# blackfin_b_flash_jtag_serial.net
KiCad netlist of a schematic drawn in Altium Designer
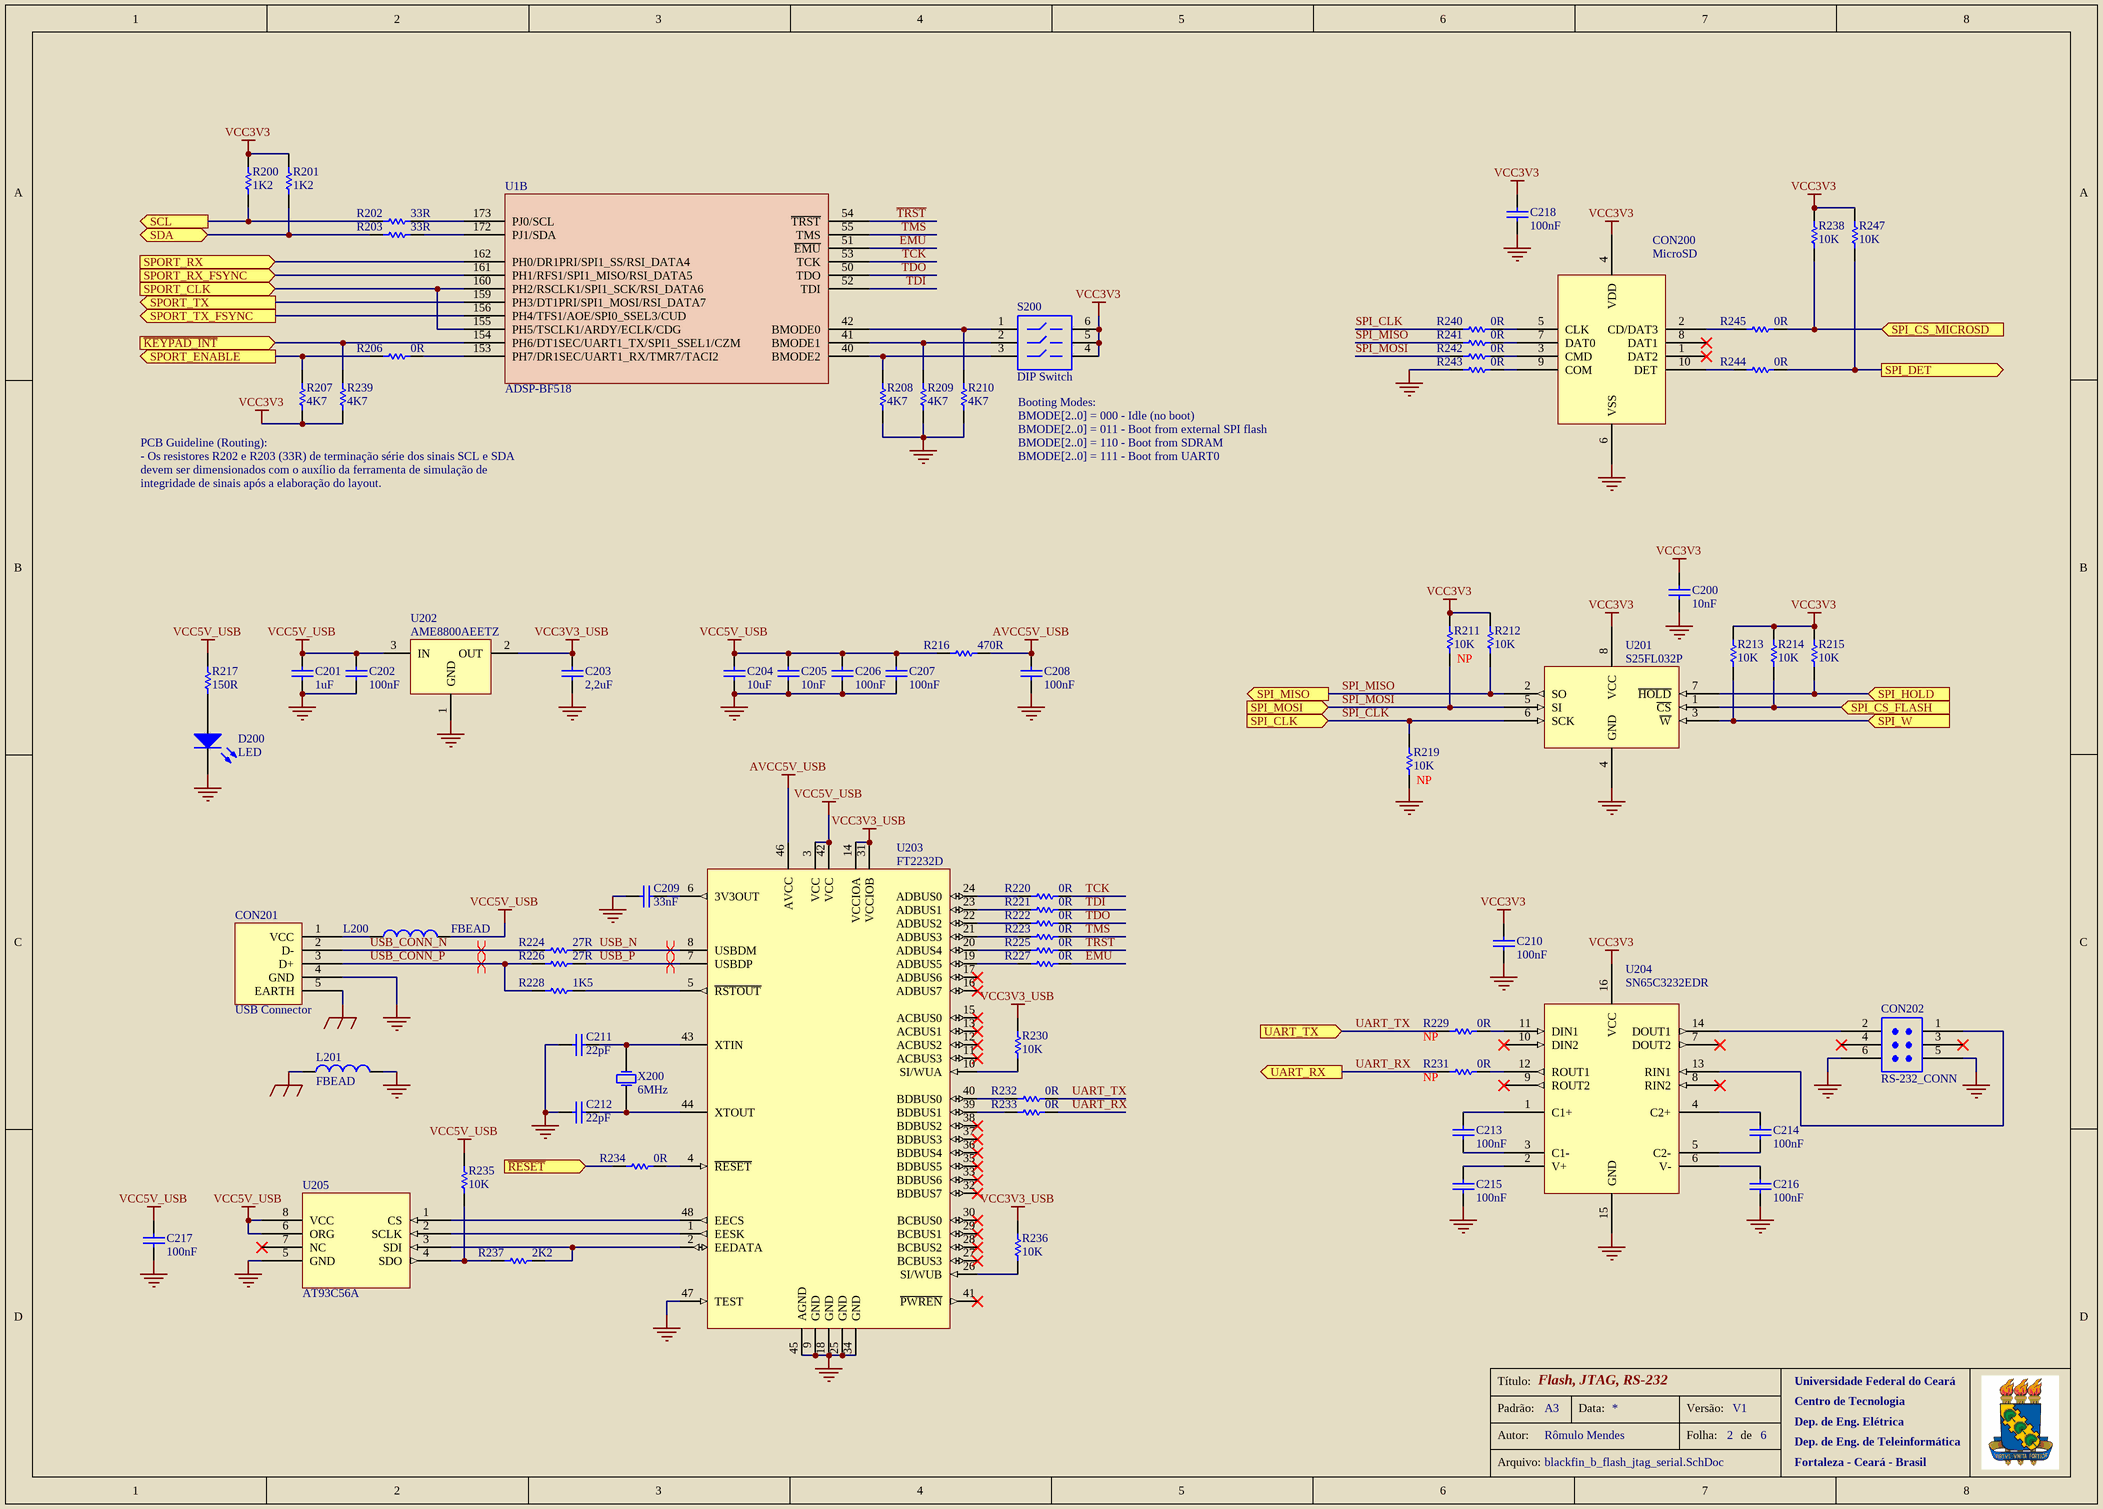
[diagram p0: blackfin_b_flash_jtag_serial.SchDoc]

(export (version "E")
  (design (tool "Eeschema 10.0.6"))
  (components
    (comp (ref "C200")
      (value "10nF")
      (footprint "blackfin_pcblib:C_0603")
      (fields
        (field (name "EVENDORPART#") "77-VJ0603Y103KXAPBC")
        (field (name "MANUFACTURER") "Vishay/Vitramon")
        (field (name "PART#") "VJ0603Y103KXAPW1BC")
      )
      (libsource (lib "blackfin_schlib") (part "Capacitor"))
    )
    (comp (ref "C201")
      (value "1uF")
      (footprint "blackfin_pcblib:C_0603")
      (fields
        (field (name "EVENDORPART#") "81-GRM188F51E105ZA12")
        (field (name "MANUFACTURER") "Murata")
        (field (name "PART#") "GRM188F51E105ZA12D")
      )
      (libsource (lib "blackfin_schlib") (part "Capacitor"))
    )
    (comp (ref "C202")
      (value "100nF")
      (footprint "blackfin_pcblib:C_0603")
      (fields
        (field (name "EVENDORPART#") "81-GRM188R71E104KA01")
        (field (name "MANUFACTURER") "Murata")
        (field (name "PART#") "GRM188R71E104KA01J")
      )
      (libsource (lib "blackfin_schlib") (part "Capacitor"))
    )
    (comp (ref "C203")
      (value "2,2uF")
      (footprint "blackfin_pcblib:C_0603")
      (fields
        (field (name "EVENDORPART#") "81-GRM188F51A225ZE01")
        (field (name "MANUFACTURER") "Murata")
        (field (name "PART#") "GRM188F51A225ZE01D")
      )
      (libsource (lib "blackfin_schlib") (part "Capacitor"))
    )
    (comp (ref "C204")
      (value "10uF")
      (footprint "blackfin_pcblib:C_0805")
      (fields
        (field (name "EVENDORPART#") "810-C2012Y5V1C106Z")
        (field (name "MANUFACTURER") "TDK")
        (field (name "PART#") "C2012Y5V1C106Z")
      )
      (libsource (lib "blackfin_schlib") (part "Capacitor"))
    )
    (comp (ref "C205")
      (value "10nF")
      (footprint "blackfin_pcblib:C_0603")
      (fields
        (field (name "EVENDORPART#") "77-VJ0603Y103KXAPBC")
        (field (name "MANUFACTURER") "Vishay/Vitramon")
        (field (name "PART#") "VJ0603Y103KXAPW1BC")
      )
      (libsource (lib "blackfin_schlib") (part "Capacitor"))
    )
    (comp (ref "C206")
      (value "100nF")
      (footprint "blackfin_pcblib:C_0603")
      (fields
        (field (name "EVENDORPART#") "81-GRM188R71E104KA01")
        (field (name "MANUFACTURER") "Murata")
        (field (name "PART#") "GRM188R71E104KA01J")
      )
      (libsource (lib "blackfin_schlib") (part "Capacitor"))
    )
    (comp (ref "C207")
      (value "100nF")
      (footprint "blackfin_pcblib:C_0603")
      (fields
        (field (name "EVENDORPART#") "81-GRM188R71E104KA01")
        (field (name "MANUFACTURER") "Murata")
        (field (name "PART#") "GRM188R71E104KA01J")
      )
      (libsource (lib "blackfin_schlib") (part "Capacitor"))
    )
    (comp (ref "C208")
      (value "100nF")
      (footprint "blackfin_pcblib:C_0603")
      (fields
        (field (name "EVENDORPART#") "81-GRM188R71E104KA01")
        (field (name "MANUFACTURER") "Murata")
        (field (name "PART#") "GRM188R71E104KA01J")
      )
      (libsource (lib "blackfin_schlib") (part "Capacitor"))
    )
    (comp (ref "C209")
      (value "33nF")
      (footprint "blackfin_pcblib:C_0603")
      (fields
        (field (name "EVENDORPART#") "81-GRM18B11E333KA01D")
        (field (name "MANUFACTURER") "Murata")
        (field (name "PART#") "GRM188B11E333KA01D")
      )
      (libsource (lib "blackfin_schlib") (part "Capacitor"))
    )
    (comp (ref "C210")
      (value "100nF")
      (footprint "blackfin_pcblib:C_0603")
      (fields
        (field (name "EVENDORPART#") "81-GRM188R71E104KA01")
        (field (name "MANUFACTURER") "Murata")
        (field (name "PART#") "GRM188R71E104KA01J")
      )
      (libsource (lib "blackfin_schlib") (part "Capacitor"))
    )
    (comp (ref "C211")
      (value "22pF")
      (footprint "blackfin_pcblib:C_0603")
      (fields
        (field (name "EVENDORPART#") "581-06035A220J")
        (field (name "MANUFACTURER") "AVX")
        (field (name "PART#") "06035A220JAT2A")
      )
      (libsource (lib "blackfin_schlib") (part "Capacitor"))
    )
    (comp (ref "C212")
      (value "22pF")
      (footprint "blackfin_pcblib:C_0603")
      (fields
        (field (name "EVENDORPART#") "581-06035A220J")
        (field (name "MANUFACTURER") "AVX")
        (field (name "PART#") "06035A220JAT2A")
      )
      (libsource (lib "blackfin_schlib") (part "Capacitor"))
    )
    (comp (ref "C213")
      (value "100nF")
      (footprint "blackfin_pcblib:C_0603")
      (fields
        (field (name "EVENDORPART#") "81-GRM188R71E104KA01")
        (field (name "MANUFACTURER") "Murata")
        (field (name "PART#") "GRM188R71E104KA01J")
      )
      (libsource (lib "blackfin_schlib") (part "Capacitor"))
    )
    (comp (ref "C214")
      (value "100nF")
      (footprint "blackfin_pcblib:C_0603")
      (fields
        (field (name "EVENDORPART#") "81-GRM188R71E104KA01")
        (field (name "MANUFACTURER") "Murata")
        (field (name "PART#") "GRM188R71E104KA01J")
      )
      (libsource (lib "blackfin_schlib") (part "Capacitor"))
    )
    (comp (ref "C215")
      (value "100nF")
      (footprint "blackfin_pcblib:C_0603")
      (fields
        (field (name "EVENDORPART#") "81-GRM188R71E104KA01")
        (field (name "MANUFACTURER") "Murata")
        (field (name "PART#") "GRM188R71E104KA01J")
      )
      (libsource (lib "blackfin_schlib") (part "Capacitor"))
    )
    (comp (ref "C216")
      (value "100nF")
      (footprint "blackfin_pcblib:C_0603")
      (fields
        (field (name "EVENDORPART#") "81-GRM188R71E104KA01")
        (field (name "MANUFACTURER") "Murata")
        (field (name "PART#") "GRM188R71E104KA01J")
      )
      (libsource (lib "blackfin_schlib") (part "Capacitor"))
    )
    (comp (ref "C217")
      (value "100nF")
      (footprint "blackfin_pcblib:C_0603")
      (fields
        (field (name "EVENDORPART#") "81-GRM188R71E104KA01")
        (field (name "MANUFACTURER") "Murata")
        (field (name "PART#") "GRM188R71E104KA01J")
      )
      (libsource (lib "blackfin_schlib") (part "Capacitor"))
    )
    (comp (ref "C218")
      (value "100nF")
      (footprint "blackfin_pcblib:C_0603")
      (fields
        (field (name "EVENDORPART#") "81-GRM188R71E104KA01")
        (field (name "MANUFACTURER") "Murata")
        (field (name "PART#") "GRM188R71E104KA01J")
      )
      (libsource (lib "blackfin_schlib") (part "Capacitor"))
    )
    (comp (ref "CON200")
      (value "MicroSD")
      (footprint "blackfin_pcblib:MICRO_SD")
      (fields
        (field (name "MANUFACTURER") "AVX Corporation")
        (field (name "PART#") "045138008010890+")
        (field (name "EVENDORPART#") "478-4965-1-ND")
      )
      (libsource (lib "blackfin_schlib") (part "MicroSD"))
    )
    (comp (ref "CON201")
      (value "USB Connector")
      (footprint "blackfin_pcblib:USB Connector")
      (fields
        (field (name "EVENDORPART#") "649-61729-0010BLF")
        (field (name "MANUFACTURER") "FCI")
        (field (name "PART#") "61729-0010BLF")
      )
      (libsource (lib "blackfin_schlib") (part "USB Connector"))
    )
    (comp (ref "CON202")
      (value "RS-232_CONN")
      (footprint "blackfin_pcblib:Header_2x3")
      (fields
        (field (name "PART#") "87759-0614")
        (field (name "EVENDORPART#") "538-87759-0614")
        (field (name "MANUFACTURER") "Molex")
      )
      (libsource (lib "blackfin_schlib") (part "RS-232 Connector"))
    )
    (comp (ref "D200")
      (value "LED")
      (footprint "blackfin_pcblib:LED_0603")
      (description "Red LED")
      (fields (field (name "EVENDORPART#") "638-QTLP600C2TR") (field (name "MANUFACTURER") "Everlight"))
      (libsource (lib "blackfin_schlib") (part "LED"))
    )
    (comp (ref "L200")
      (value "FBEAD")
      (footprint "blackfin_pcblib:L_0603")
      (fields
        (field (name "EVENDORPART#") "875-MI0603L301R-10")
        (field (name "MANUFACTURER") "Laird Technologies")
        (field (name "PART#") "MI0603L301R-10")
      )
      (libsource (lib "blackfin_schlib") (part "Inductor"))
    )
    (comp (ref "L201")
      (value "FBEAD")
      (footprint "blackfin_pcblib:L_0603")
      (fields
        (field (name "EVENDORPART#") "875-MI0603L301R-10")
        (field (name "MANUFACTURER") "Laird Technologies")
        (field (name "PART#") "MI0603L301R-10")
      )
      (libsource (lib "blackfin_schlib") (part "Inductor"))
    )
    (comp (ref "R200")
      (value "1K2")
      (footprint "blackfin_pcblib:R_0603")
      (fields
        (field (name "EVENDORPART#") "71-CRCW0603-1.2K-E3")
        (field (name "PART#") "CRCW06031K20FKEA")
        (field (name "MANUFACTURER") "Vishay/Dale")
      )
      (libsource (lib "blackfin_schlib") (part "Resistor"))
    )
    (comp (ref "R201")
      (value "1K2")
      (footprint "blackfin_pcblib:R_0603")
      (fields
        (field (name "EVENDORPART#") "71-CRCW0603-1.2K-E3")
        (field (name "PART#") "CRCW06031K20FKEA")
        (field (name "MANUFACTURER") "Vishay/Dale")
      )
      (libsource (lib "blackfin_schlib") (part "Resistor"))
    )
    (comp (ref "R202")
      (value "33R")
      (footprint "blackfin_pcblib:R_0402")
      (fields
        (field (name "EVENDORPART#") "71-CRCW0402J-33-E3")
        (field (name "PART#") "CRCW040233R0JNED")
        (field (name "MANUFACTURER") "Vishay/Dale")
      )
      (libsource (lib "blackfin_schlib") (part "Resistor"))
    )
    (comp (ref "R203")
      (value "33R")
      (footprint "blackfin_pcblib:R_0402")
      (fields
        (field (name "EVENDORPART#") "71-CRCW0402J-33-E3")
        (field (name "PART#") "CRCW040233R0JNED")
        (field (name "MANUFACTURER") "Vishay/Dale")
      )
      (libsource (lib "blackfin_schlib") (part "Resistor"))
    )
    (comp (ref "R206")
      (value "0R")
      (footprint "blackfin_pcblib:R_0603")
      (fields
        (field (name "EVENDORPART#") "71-CRCW06030000Z0EB")
        (field (name "PART#") "CRCW06030000Z0EB")
        (field (name "MANUFACTURER") "Vishay/Dale")
      )
      (libsource (lib "blackfin_schlib") (part "Resistor"))
    )
    (comp (ref "R207")
      (value "4K7")
      (footprint "blackfin_pcblib:R_0603")
      (fields
        (field (name "EVENDORPART#") "71-CRCW0603J-4.7K-E3")
        (field (name "PART#") "CRCW06034K70JNEA")
        (field (name "MANUFACTURER") "Vishay/Dale")
      )
      (libsource (lib "blackfin_schlib") (part "Resistor"))
    )
    (comp (ref "R208")
      (value "4K7")
      (footprint "blackfin_pcblib:R_0603")
      (fields
        (field (name "EVENDORPART#") "71-CRCW0603J-4.7K-E3")
        (field (name "PART#") "CRCW06034K70JNEA")
        (field (name "MANUFACTURER") "Vishay/Dale")
      )
      (libsource (lib "blackfin_schlib") (part "Resistor"))
    )
    (comp (ref "R209")
      (value "4K7")
      (footprint "blackfin_pcblib:R_0603")
      (fields
        (field (name "EVENDORPART#") "71-CRCW0603J-4.7K-E3")
        (field (name "PART#") "CRCW06034K70JNEA")
        (field (name "MANUFACTURER") "Vishay/Dale")
      )
      (libsource (lib "blackfin_schlib") (part "Resistor"))
    )
    (comp (ref "R210")
      (value "4K7")
      (footprint "blackfin_pcblib:R_0603")
      (fields
        (field (name "EVENDORPART#") "71-CRCW0603J-4.7K-E3")
        (field (name "PART#") "CRCW06034K70JNEA")
        (field (name "MANUFACTURER") "Vishay/Dale")
      )
      (libsource (lib "blackfin_schlib") (part "Resistor"))
    )
    (comp (ref "R211")
      (value "10K")
      (footprint "blackfin_pcblib:R_0603")
      (fields
        (field (name "EVENDORPART#") "71-CRCW0603-10K-E3")
        (field (name "PART#") "CRCW060310K0FKEA")
        (field (name "MANUFACTURER") "Vishay/Dale")
      )
      (libsource (lib "blackfin_schlib") (part "Resistor"))
    )
    (comp (ref "R212")
      (value "10K")
      (footprint "blackfin_pcblib:R_0603")
      (fields
        (field (name "EVENDORPART#") "71-CRCW0603-10K-E3")
        (field (name "PART#") "CRCW060310K0FKEA")
        (field (name "MANUFACTURER") "Vishay/Dale")
      )
      (libsource (lib "blackfin_schlib") (part "Resistor"))
    )
    (comp (ref "R213")
      (value "10K")
      (footprint "blackfin_pcblib:R_0603")
      (fields
        (field (name "EVENDORPART#") "71-CRCW0603-10K-E3")
        (field (name "PART#") "CRCW060310K0FKEA")
        (field (name "MANUFACTURER") "Vishay/Dale")
      )
      (libsource (lib "blackfin_schlib") (part "Resistor"))
    )
    (comp (ref "R214")
      (value "10K")
      (footprint "blackfin_pcblib:R_0603")
      (fields
        (field (name "EVENDORPART#") "71-CRCW0603-10K-E3")
        (field (name "PART#") "CRCW060310K0FKEA")
        (field (name "MANUFACTURER") "Vishay/Dale")
      )
      (libsource (lib "blackfin_schlib") (part "Resistor"))
    )
    (comp (ref "R215")
      (value "10K")
      (footprint "blackfin_pcblib:R_0603")
      (fields
        (field (name "EVENDORPART#") "71-CRCW0603-10K-E3")
        (field (name "PART#") "CRCW060310K0FKEA")
        (field (name "MANUFACTURER") "Vishay/Dale")
      )
      (libsource (lib "blackfin_schlib") (part "Resistor"))
    )
    (comp (ref "R216")
      (value "470R")
      (footprint "blackfin_pcblib:R_0603")
      (fields
        (field (name "EVENDORPART#") "71-CRCW0603-470-E3")
        (field (name "PART#") "CRCW0603470RFKEA")
        (field (name "MANUFACTURER") "Vishay/Dale")
      )
      (libsource (lib "blackfin_schlib") (part "Resistor"))
    )
    (comp (ref "R217")
      (value "150R")
      (footprint "blackfin_pcblib:R_0603")
      (fields
        (field (name "EVENDORPART#") "71-CRCW0603150RJNEB")
        (field (name "PART#") "CRCW0603150RJNEB")
        (field (name "MANUFACTURER") "Vishay/Dale")
      )
      (libsource (lib "blackfin_schlib") (part "Resistor"))
    )
    (comp (ref "R219")
      (value "10K")
      (footprint "blackfin_pcblib:R_0603")
      (fields
        (field (name "EVENDORPART#") "71-CRCW0603-10K-E3")
        (field (name "PART#") "CRCW060310K0FKEA")
        (field (name "MANUFACTURER") "Vishay/Dale")
      )
      (libsource (lib "blackfin_schlib") (part "Resistor"))
    )
    (comp (ref "R220")
      (value "0R")
      (footprint "blackfin_pcblib:R_0603")
      (fields
        (field (name "EVENDORPART#") "71-CRCW06030000Z0EB")
        (field (name "PART#") "CRCW06030000Z0EB")
        (field (name "MANUFACTURER") "Vishay/Dale")
      )
      (libsource (lib "blackfin_schlib") (part "Resistor"))
    )
    (comp (ref "R221")
      (value "0R")
      (footprint "blackfin_pcblib:R_0603")
      (fields
        (field (name "EVENDORPART#") "71-CRCW06030000Z0EB")
        (field (name "PART#") "CRCW06030000Z0EB")
        (field (name "MANUFACTURER") "Vishay/Dale")
      )
      (libsource (lib "blackfin_schlib") (part "Resistor"))
    )
    (comp (ref "R222")
      (value "0R")
      (footprint "blackfin_pcblib:R_0603")
      (fields
        (field (name "EVENDORPART#") "71-CRCW06030000Z0EB")
        (field (name "PART#") "CRCW06030000Z0EB")
        (field (name "MANUFACTURER") "Vishay/Dale")
      )
      (libsource (lib "blackfin_schlib") (part "Resistor"))
    )
    (comp (ref "R223")
      (value "0R")
      (footprint "blackfin_pcblib:R_0603")
      (fields
        (field (name "EVENDORPART#") "71-CRCW06030000Z0EB")
        (field (name "PART#") "CRCW06030000Z0EB")
        (field (name "MANUFACTURER") "Vishay/Dale")
      )
      (libsource (lib "blackfin_schlib") (part "Resistor"))
    )
    (comp (ref "R224")
      (value "27R")
      (footprint "blackfin_pcblib:R_0603")
      (fields
        (field (name "EVENDORPART#") "71-CRCW0603-27-E3")
        (field (name "PART#") "CRCW060327R0FKEA")
        (field (name "MANUFACTURER") "Vishay/Dale")
      )
      (libsource (lib "blackfin_schlib") (part "Resistor"))
    )
    (comp (ref "R225")
      (value "0R")
      (footprint "blackfin_pcblib:R_0603")
      (fields
        (field (name "EVENDORPART#") "71-CRCW06030000Z0EB")
        (field (name "PART#") "CRCW06030000Z0EB")
        (field (name "MANUFACTURER") "Vishay/Dale")
      )
      (libsource (lib "blackfin_schlib") (part "Resistor"))
    )
    (comp (ref "R226")
      (value "27R")
      (footprint "blackfin_pcblib:R_0603")
      (fields
        (field (name "EVENDORPART#") "71-CRCW0603-27-E3")
        (field (name "PART#") "CRCW060327R0FKEA")
        (field (name "MANUFACTURER") "Vishay/Dale")
      )
      (libsource (lib "blackfin_schlib") (part "Resistor"))
    )
    (comp (ref "R227")
      (value "0R")
      (footprint "blackfin_pcblib:R_0603")
      (fields
        (field (name "EVENDORPART#") "71-CRCW06030000Z0EB")
        (field (name "PART#") "CRCW06030000Z0EB")
        (field (name "MANUFACTURER") "Vishay/Dale")
      )
      (libsource (lib "blackfin_schlib") (part "Resistor"))
    )
    (comp (ref "R228")
      (value "1K5")
      (footprint "blackfin_pcblib:R_0603")
      (fields
        (field (name "EVENDORPART#") "71-CRCW0603-1.5K-E3")
        (field (name "PART#") "CRCW06031K50FKEA")
        (field (name "MANUFACTURER") "Vishay/Dale")
      )
      (libsource (lib "blackfin_schlib") (part "Resistor"))
    )
    (comp (ref "R229")
      (value "0R")
      (footprint "blackfin_pcblib:R_0603")
      (fields
        (field (name "EVENDORPART#") "71-CRCW06030000Z0EB")
        (field (name "PART#") "CRCW06030000Z0EB")
        (field (name "MANUFACTURER") "Vishay/Dale")
      )
      (libsource (lib "blackfin_schlib") (part "Resistor"))
    )
    (comp (ref "R230")
      (value "10K")
      (footprint "blackfin_pcblib:R_0603")
      (fields
        (field (name "EVENDORPART#") "71-CRCW0603-10K-E3")
        (field (name "PART#") "CRCW060310K0FKEA")
        (field (name "MANUFACTURER") "Vishay/Dale")
      )
      (libsource (lib "blackfin_schlib") (part "Resistor"))
    )
    (comp (ref "R231")
      (value "0R")
      (footprint "blackfin_pcblib:R_0603")
      (fields
        (field (name "EVENDORPART#") "71-CRCW06030000Z0EB")
        (field (name "PART#") "CRCW06030000Z0EB")
        (field (name "MANUFACTURER") "Vishay/Dale")
      )
      (libsource (lib "blackfin_schlib") (part "Resistor"))
    )
    (comp (ref "R232")
      (value "0R")
      (footprint "blackfin_pcblib:R_0603")
      (fields
        (field (name "EVENDORPART#") "71-CRCW06030000Z0EB")
        (field (name "PART#") "CRCW06030000Z0EB")
        (field (name "MANUFACTURER") "Vishay/Dale")
      )
      (libsource (lib "blackfin_schlib") (part "Resistor"))
    )
    (comp (ref "R233")
      (value "0R")
      (footprint "blackfin_pcblib:R_0603")
      (fields
        (field (name "EVENDORPART#") "71-CRCW06030000Z0EB")
        (field (name "PART#") "CRCW06030000Z0EB")
        (field (name "MANUFACTURER") "Vishay/Dale")
      )
      (libsource (lib "blackfin_schlib") (part "Resistor"))
    )
    (comp (ref "R234")
      (value "0R")
      (footprint "blackfin_pcblib:R_0603")
      (fields
        (field (name "EVENDORPART#") "71-CRCW06030000Z0EB")
        (field (name "PART#") "CRCW06030000Z0EB")
        (field (name "MANUFACTURER") "Vishay/Dale")
      )
      (libsource (lib "blackfin_schlib") (part "Resistor"))
    )
    (comp (ref "R235")
      (value "10K")
      (footprint "blackfin_pcblib:R_0603")
      (fields
        (field (name "EVENDORPART#") "71-CRCW0603-10K-E3")
        (field (name "PART#") "CRCW060310K0FKEA")
        (field (name "MANUFACTURER") "Vishay/Dale")
      )
      (libsource (lib "blackfin_schlib") (part "Resistor"))
    )
    (comp (ref "R236")
      (value "10K")
      (footprint "blackfin_pcblib:R_0603")
      (fields
        (field (name "EVENDORPART#") "71-CRCW0603-10K-E3")
        (field (name "PART#") "CRCW060310K0FKEA")
        (field (name "MANUFACTURER") "Vishay/Dale")
      )
      (libsource (lib "blackfin_schlib") (part "Resistor"))
    )
    (comp (ref "R237")
      (value "2K2")
      (footprint "blackfin_pcblib:R_0603")
      (fields
        (field (name "EVENDORPART#") "71-CRCW06032K20JNEB")
        (field (name "PART#") "CRCW06032K20JNEB")
        (field (name "MANUFACTURER") "Vishay/Dale")
      )
      (libsource (lib "blackfin_schlib") (part "Resistor"))
    )
    (comp (ref "R238")
      (value "10K")
      (footprint "blackfin_pcblib:R_0603")
      (fields
        (field (name "EVENDORPART#") "71-CRCW0603-10K-E3")
        (field (name "PART#") "CRCW060310K0FKEA")
        (field (name "MANUFACTURER") "Vishay/Dale")
      )
      (libsource (lib "blackfin_schlib") (part "Resistor"))
    )
    (comp (ref "R239")
      (value "4K7")
      (footprint "blackfin_pcblib:R_0603")
      (fields
        (field (name "EVENDORPART#") "71-CRCW0603J-4.7K-E3")
        (field (name "PART#") "CRCW06034K70JNEA")
        (field (name "MANUFACTURER") "Vishay/Dale")
      )
      (libsource (lib "blackfin_schlib") (part "Resistor"))
    )
    (comp (ref "R240")
      (value "0R")
      (footprint "blackfin_pcblib:R_0603")
      (fields
        (field (name "EVENDORPART#") "71-CRCW06030000Z0EB")
        (field (name "PART#") "CRCW06030000Z0EB")
        (field (name "MANUFACTURER") "Vishay/Dale")
      )
      (libsource (lib "blackfin_schlib") (part "Resistor"))
    )
    (comp (ref "R241")
      (value "0R")
      (footprint "blackfin_pcblib:R_0603")
      (fields
        (field (name "EVENDORPART#") "71-CRCW06030000Z0EB")
        (field (name "PART#") "CRCW06030000Z0EB")
        (field (name "MANUFACTURER") "Vishay/Dale")
      )
      (libsource (lib "blackfin_schlib") (part "Resistor"))
    )
    (comp (ref "R242")
      (value "0R")
      (footprint "blackfin_pcblib:R_0603")
      (fields
        (field (name "EVENDORPART#") "71-CRCW06030000Z0EB")
        (field (name "PART#") "CRCW06030000Z0EB")
        (field (name "MANUFACTURER") "Vishay/Dale")
      )
      (libsource (lib "blackfin_schlib") (part "Resistor"))
    )
    (comp (ref "R243")
      (value "0R")
      (footprint "blackfin_pcblib:R_0603")
      (fields
        (field (name "EVENDORPART#") "71-CRCW06030000Z0EB")
        (field (name "PART#") "CRCW06030000Z0EB")
        (field (name "MANUFACTURER") "Vishay/Dale")
      )
      (libsource (lib "blackfin_schlib") (part "Resistor"))
    )
    (comp (ref "R244")
      (value "0R")
      (footprint "blackfin_pcblib:R_0603")
      (fields
        (field (name "EVENDORPART#") "71-CRCW06030000Z0EB")
        (field (name "PART#") "CRCW06030000Z0EB")
        (field (name "MANUFACTURER") "Vishay/Dale")
      )
      (libsource (lib "blackfin_schlib") (part "Resistor"))
    )
    (comp (ref "R245")
      (value "0R")
      (footprint "blackfin_pcblib:R_0603")
      (fields
        (field (name "EVENDORPART#") "71-CRCW06030000Z0EB")
        (field (name "PART#") "CRCW06030000Z0EB")
        (field (name "MANUFACTURER") "Vishay/Dale")
      )
      (libsource (lib "blackfin_schlib") (part "Resistor"))
    )
    (comp (ref "R247")
      (value "10K")
      (footprint "blackfin_pcblib:R_0603")
      (fields
        (field (name "EVENDORPART#") "71-CRCW0603-10K-E3")
        (field (name "PART#") "CRCW060310K0FKEA")
        (field (name "MANUFACTURER") "Vishay/Dale")
      )
      (libsource (lib "blackfin_schlib") (part "Resistor"))
    )
    (comp (ref "S200")
      (value "DIP Switch")
      (footprint "blackfin_pcblib:DIP Switch")
      (fields
        (field (name "EVENDORPART#") "611-SDA03H1SBD")
        (field (name "MANUFACTURER") "C&K Components")
        (field (name "PART#") "SDA03H1SBD")
      )
      (libsource (lib "*") (part "DIP Switch"))
    )
    (comp (ref "U1")
      (value "ADSP-BF518")
      (footprint "blackfin_pcblib:LQFP-176")
      (fields (field (name "EVENDORPART#") "ADSP-BF518BSWZ-4") (field (name "MANUFACTURER") "Analog Devices"))
      (libsource (lib "blackfin_schlib") (part "ADSP-BF518"))
    )
    (comp (ref "U201")
      (value "S25FL032P")
      (footprint "blackfin_pcblib:SO-8")
      (fields (field (name "PART#") "S25FL032P0XMFI010") (field (name "MANUFACTURER") "Spansion"))
      (libsource (lib "blackfin_schlib") (part "S25FL032P"))
    )
    (comp (ref "U202")
      (value "AME8800AEETZ")
      (footprint "blackfin_pcblib:SOT-23")
      (fields (field (name "EVENDORPART#") "827-AME8800AEETZ") (field (name "MANUFACTURER") "AME"))
      (libsource (lib "blackfin_schlib") (part "AME8800AEETZ"))
    )
    (comp (ref "U203")
      (value "FT2232D")
      (footprint "blackfin_pcblib:LQFP-48")
      (fields (field (name "EVENDORPART#") "895-FT2232D") (field (name "MANUFACTURER") "FTDI"))
      (libsource (lib "blackfin_schlib") (part "FT2232D"))
    )
    (comp (ref "U204")
      (value "SN65C3232EDR")
      (footprint "blackfin_pcblib:SOIC-16")
      (fields
        (field (name "EVENDORPART#") "595-SN65C3232EDR")
        (field (name "MANUFACTURER") "Texas Instruments")
      )
      (libsource (lib "blackfin_schlib") (part "RS-232 Transceiver"))
    )
    (comp (ref "U205")
      (value "AT93C56A")
      (footprint "blackfin_pcblib:SOIC-8 (AT93C56A)")
      (fields
        (field (name "EVENDORPART#") "556-A93C56A10SU2.7")
        (field (name "MANUFACTURER") "Atmel")
        (field (name "PART#") "AT93C56A-10SU-2.7")
      )
      (libsource (lib "blackfin_schlib") (part "AT93C56A"))
    )
    (comp (ref "X200")
      (value "6MHz")
      (footprint "blackfin_pcblib:XTAL_6MHz")
      (fields
        (field (name "EVENDORPART#") "774-ATS060SM-1")
        (field (name "PART#") "ATS060SM-1")
        (field (name "MANUFACTURER") "CTS Electronic Components")
      )
      (libsource (lib "blackfin_schlib") (part "XTAL"))
    )
  )
  (nets
    (net (code "1") (name "/SCL") (class "Default")
      (node (ref "R200") (pin "1") (pinfunction "1_1") (pintype "passive"))
      (node (ref "R202") (pin "1") (pinfunction "1_1") (pintype "passive"))
    )
    (net (code "2") (name "/SDA") (class "Default")
      (node (ref "R201") (pin "1") (pinfunction "1_1") (pintype "passive"))
      (node (ref "R203") (pin "1") (pinfunction "1_1") (pintype "passive"))
    )
    (net (code "3") (name "/SPI_CLK") (class "Default")
      (node (ref "R219") (pin "2") (pinfunction "2_2") (pintype "passive"))
      (node (ref "R240") (pin "1") (pinfunction "1_1") (pintype "passive"))
      (node (ref "U201") (pin "6") (pinfunction "SCK_6") (pintype "input"))
    )
    (net (code "4") (name "/SPI_CS_FLASH") (class "Default")
      (node (ref "R214") (pin "1") (pinfunction "1_1") (pintype "passive"))
      (node (ref "U201") (pin "1") (pinfunction "~{CS}_1") (pintype "input"))
    )
    (net (code "5") (name "/SPI_CS_MICROSD") (class "Default")
      (node (ref "R238") (pin "1") (pinfunction "1_1") (pintype "passive"))
      (node (ref "R245") (pin "2") (pinfunction "2_2") (pintype "passive"))
    )
    (net (code "6") (name "/SPI_DET") (class "Default")
      (node (ref "R244") (pin "2") (pinfunction "2_2") (pintype "passive"))
      (node (ref "R247") (pin "1") (pinfunction "1_1") (pintype "passive"))
    )
    (net (code "7") (name "/SPI_HOLD") (class "Default")
      (node (ref "R215") (pin "1") (pinfunction "1_1") (pintype "passive"))
      (node (ref "U201") (pin "7") (pinfunction "~{HOLD}_7") (pintype "input"))
    )
    (net (code "8") (name "/SPI_MISO") (class "Default")
      (node (ref "R212") (pin "1") (pinfunction "1_1") (pintype "passive"))
      (node (ref "R241") (pin "1") (pinfunction "1_1") (pintype "passive"))
      (node (ref "U201") (pin "2") (pinfunction "SO_2") (pintype "output"))
    )
    (net (code "9") (name "/SPI_MOSI") (class "Default")
      (node (ref "R211") (pin "1") (pinfunction "1_1") (pintype "passive"))
      (node (ref "R242") (pin "1") (pinfunction "1_1") (pintype "passive"))
      (node (ref "U201") (pin "5") (pinfunction "SI_5") (pintype "input"))
    )
    (net (code "10") (name "/SPI_W") (class "Default")
      (node (ref "R213") (pin "1") (pinfunction "1_1") (pintype "passive"))
      (node (ref "U201") (pin "3") (pinfunction "~{W}_3") (pintype "input"))
    )
    (net (code "11") (name "/SPORT_CLK") (class "Default")
      (node (ref "U1") (pin "155") (pinfunction "PH5/TSCLK1/ARDY/ECLK/CDG_155") (pintype "passive"))
      (node (ref "U1") (pin "160") (pinfunction "PH2/RSCLK1/SPI1_SCK/RSI_DATA6_160") (pintype "passive"))
    )
    (net (code "12") (name "/SPORT_ENABLE") (class "Default")
      (node (ref "R206") (pin "1") (pinfunction "1_1") (pintype "passive"))
      (node (ref "R207") (pin "2") (pinfunction "2_2") (pintype "passive"))
    )
    (net (code "13") (name "/SPORT_RX") (class "Default")
      (node (ref "U1") (pin "162") (pinfunction "PH0/DR1PRI/SPI1_SS/RSI_DATA4_162") (pintype "passive"))
    )
    (net (code "14") (name "/SPORT_RX_FSYNC") (class "Default")
      (node (ref "U1") (pin "161") (pinfunction "PH1/RFS1/SPI1_MISO/RSI_DATA5_161") (pintype "passive"))
    )
    (net (code "15") (name "/SPORT_TX") (class "Default")
      (node (ref "U1") (pin "159") (pinfunction "PH3/DT1PRI/SPI1_MOSI/RSI_DATA7_159") (pintype "passive"))
    )
    (net (code "16") (name "/SPORT_TX_FSYNC") (class "Default")
      (node (ref "U1") (pin "156") (pinfunction "PH4/TFS1/AOE/SPI0_SSEL3/CUD_156") (pintype "passive"))
    )
    (net (code "17") (name "/TCK") (class "Default")
      (node (ref "R220") (pin "2") (pinfunction "2_2") (pintype "passive"))
      (node (ref "U1") (pin "53") (pinfunction "TCK_53") (pintype "passive"))
    )
    (net (code "18") (name "/TDI") (class "Default")
      (node (ref "R221") (pin "2") (pinfunction "2_2") (pintype "passive"))
      (node (ref "U1") (pin "52") (pinfunction "TDI_52") (pintype "passive"))
    )
    (net (code "19") (name "/TDO") (class "Default")
      (node (ref "R222") (pin "2") (pinfunction "2_2") (pintype "passive"))
      (node (ref "U1") (pin "50") (pinfunction "TDO_50") (pintype "passive"))
    )
    (net (code "20") (name "/TMS") (class "Default")
      (node (ref "R223") (pin "2") (pinfunction "2_2") (pintype "passive"))
      (node (ref "U1") (pin "55") (pinfunction "TMS_55") (pintype "passive"))
    )
    (net (code "21") (name "/UART_RX") (class "Default")
      (node (ref "R231") (pin "1") (pinfunction "1_1") (pintype "passive"))
      (node (ref "R233") (pin "2") (pinfunction "2_2") (pintype "passive"))
    )
    (net (code "22") (name "/UART_TX") (class "Default")
      (node (ref "R229") (pin "1") (pinfunction "1_1") (pintype "passive"))
      (node (ref "R232") (pin "2") (pinfunction "2_2") (pintype "passive"))
    )
    (net (code "23") (name "/USB_CONN_N") (class "Default")
      (node (ref "CON201") (pin "2") (pinfunction "D-_2") (pintype "passive"))
      (node (ref "R224") (pin "1") (pinfunction "1_1") (pintype "passive"))
    )
    (net (code "24") (name "/USB_CONN_P") (class "Default")
      (node (ref "CON201") (pin "3") (pinfunction "D+_3") (pintype "passive"))
      (node (ref "R226") (pin "1") (pinfunction "1_1") (pintype "passive"))
      (node (ref "R228") (pin "1") (pinfunction "1_1") (pintype "passive"))
    )
    (net (code "25") (name "/USB_N") (class "Default")
      (node (ref "R224") (pin "2") (pinfunction "2_2") (pintype "passive"))
      (node (ref "U203") (pin "8") (pinfunction "USBDM_8") (pintype "passive"))
    )
    (net (code "26") (name "/USB_P") (class "Default")
      (node (ref "R226") (pin "2") (pinfunction "2_2") (pintype "passive"))
      (node (ref "U203") (pin "7") (pinfunction "USBDP_7") (pintype "passive"))
    )
    (net (code "27") (name "/~{EMU}") (class "Default")
      (node (ref "R227") (pin "2") (pinfunction "2_2") (pintype "passive"))
      (node (ref "U1") (pin "51") (pinfunction "~{EMU}_51") (pintype "passive"))
    )
    (net (code "28") (name "/~{KEYPAD_INT}") (class "Default")
      (node (ref "R239") (pin "2") (pinfunction "2_2") (pintype "passive"))
      (node (ref "U1") (pin "154") (pinfunction "PH6/DT1SEC/UART1_TX/SPI1_SSEL1/CZM_154") (pintype "passive"))
    )
    (net (code "29") (name "/~{RESET}") (class "Default")
      (node (ref "R234") (pin "1") (pinfunction "1_1") (pintype "passive"))
    )
    (net (code "30") (name "/~{TRST}") (class "Default")
      (node (ref "R225") (pin "2") (pinfunction "2_2") (pintype "passive"))
      (node (ref "U1") (pin "54") (pinfunction "~{TRST}_54") (pintype "passive"))
    )
    (net (code "31") (name "AVCC5V_USB") (class "Default")
      (node (ref "C208") (pin "2") (pinfunction "2_2") (pintype "passive"))
      (node (ref "R216") (pin "2") (pinfunction "2_2") (pintype "passive"))
      (node (ref "U203") (pin "46") (pinfunction "AVCC_46") (pintype "power_in"))
    )
    (net (code "32") (name "EARTH_USB") (class "Default")
      (node (ref "CON201") (pin "5") (pinfunction "EARTH_5") (pintype "passive"))
      (node (ref "L201") (pin "1") (pinfunction "1_1") (pintype "passive"))
    )
    (net (code "33") (name "GND") (class "Default")
      (node (ref "C200") (pin "1") (pinfunction "1_1") (pintype "passive"))
      (node (ref "C201") (pin "1") (pinfunction "1_1") (pintype "passive"))
      (node (ref "C202") (pin "1") (pinfunction "1_1") (pintype "passive"))
      (node (ref "C203") (pin "1") (pinfunction "1_1") (pintype "passive"))
      (node (ref "C204") (pin "1") (pinfunction "1_1") (pintype "passive"))
      (node (ref "C205") (pin "1") (pinfunction "1_1") (pintype "passive"))
      (node (ref "C206") (pin "1") (pinfunction "1_1") (pintype "passive"))
      (node (ref "C207") (pin "1") (pinfunction "1_1") (pintype "passive"))
      (node (ref "C208") (pin "1") (pinfunction "1_1") (pintype "passive"))
      (node (ref "C209") (pin "2") (pinfunction "2_2") (pintype "passive"))
      (node (ref "C210") (pin "1") (pinfunction "1_1") (pintype "passive"))
      (node (ref "C211") (pin "2") (pinfunction "2_2") (pintype "passive"))
      (node (ref "C212") (pin "2") (pinfunction "2_2") (pintype "passive"))
      (node (ref "C215") (pin "1") (pinfunction "1_1") (pintype "passive"))
      (node (ref "C216") (pin "1") (pinfunction "1_1") (pintype "passive"))
      (node (ref "C217") (pin "1") (pinfunction "1_1") (pintype "passive"))
      (node (ref "C218") (pin "1") (pinfunction "1_1") (pintype "passive"))
      (node (ref "CON200") (pin "6") (pinfunction "VSS_6") (pintype "passive"))
      (node (ref "CON201") (pin "4") (pinfunction "GND_4") (pintype "passive"))
      (node (ref "CON202") (pin "5") (pinfunction "GND_5") (pintype "passive"))
      (node (ref "CON202") (pin "6") (pinfunction "GND_6") (pintype "passive"))
      (node (ref "D200") (pin "2") (pinfunction "K_2") (pintype "passive"))
      (node (ref "L201") (pin "2") (pinfunction "2_2") (pintype "passive"))
      (node (ref "R208") (pin "1") (pinfunction "1_1") (pintype "passive"))
      (node (ref "R209") (pin "1") (pinfunction "1_1") (pintype "passive"))
      (node (ref "R210") (pin "1") (pinfunction "1_1") (pintype "passive"))
      (node (ref "R219") (pin "1") (pinfunction "1_1") (pintype "passive"))
      (node (ref "R243") (pin "1") (pinfunction "1_1") (pintype "passive"))
      (node (ref "U201") (pin "4") (pinfunction "GND_4") (pintype "power_in"))
      (node (ref "U202") (pin "1") (pinfunction "GND_1") (pintype "passive"))
      (node (ref "U203") (pin "18") (pinfunction "GND_18") (pintype "power_in"))
      (node (ref "U203") (pin "25") (pinfunction "GND_25") (pintype "power_in"))
      (node (ref "U203") (pin "34") (pinfunction "GND_34") (pintype "power_in"))
      (node (ref "U203") (pin "45") (pinfunction "AGND_45") (pintype "power_in"))
      (node (ref "U203") (pin "47") (pinfunction "TEST_47") (pintype "input"))
      (node (ref "U203") (pin "9") (pinfunction "GND_9") (pintype "power_in"))
      (node (ref "U204") (pin "15") (pinfunction "GND_15") (pintype "power_in"))
      (node (ref "U205") (pin "5") (pinfunction "GND_5") (pintype "power_in"))
    )
    (net (code "34") (name "Net-(CON200-CD{slash}DAT3)") (class "Default")
      (node (ref "CON200") (pin "2") (pinfunction "CD/DAT3_2") (pintype "passive"))
      (node (ref "R245") (pin "1") (pinfunction "1_1") (pintype "passive"))
    )
    (net (code "35") (name "Net-(CON200-CLK)") (class "Default")
      (node (ref "CON200") (pin "5") (pinfunction "CLK_5") (pintype "passive"))
      (node (ref "R240") (pin "2") (pinfunction "2_2") (pintype "passive"))
    )
    (net (code "36") (name "Net-(CON200-CMD)") (class "Default")
      (node (ref "CON200") (pin "3") (pinfunction "CMD_3") (pintype "passive"))
      (node (ref "R242") (pin "2") (pinfunction "2_2") (pintype "passive"))
    )
    (net (code "37") (name "Net-(CON200-COM)") (class "Default")
      (node (ref "CON200") (pin "9") (pinfunction "COM_9") (pintype "passive"))
      (node (ref "R243") (pin "2") (pinfunction "2_2") (pintype "passive"))
    )
    (net (code "38") (name "Net-(CON200-DAT0)") (class "Default")
      (node (ref "CON200") (pin "7") (pinfunction "DAT0_7") (pintype "passive"))
      (node (ref "R241") (pin "2") (pinfunction "2_2") (pintype "passive"))
    )
    (net (code "39") (name "Net-(CON200-DET)") (class "Default")
      (node (ref "CON200") (pin "10") (pinfunction "DET_10") (pintype "passive"))
      (node (ref "R244") (pin "1") (pinfunction "1_1") (pintype "passive"))
    )
    (net (code "40") (name "Net-(CON201-VCC)") (class "Default")
      (node (ref "CON201") (pin "1") (pinfunction "VCC_1") (pintype "passive"))
      (node (ref "L200") (pin "1") (pinfunction "1_1") (pintype "passive"))
    )
    (net (code "41") (name "Net-(CON202-RX)") (class "Default")
      (node (ref "CON202") (pin "2") (pinfunction "RX_2") (pintype "passive"))
      (node (ref "U204") (pin "14") (pinfunction "DOUT1_14") (pintype "output"))
    )
    (net (code "42") (name "Net-(CON202-TX)") (class "Default")
      (node (ref "CON202") (pin "1") (pinfunction "TX_1") (pintype "passive"))
      (node (ref "U204") (pin "13") (pinfunction "RIN1_13") (pintype "input"))
    )
    (net (code "43") (name "Net-(D200-A)") (class "Default")
      (node (ref "D200") (pin "1") (pinfunction "A_1") (pintype "passive"))
      (node (ref "R217") (pin "1") (pinfunction "1_1") (pintype "passive"))
    )
    (net (code "44") (name "Net-(U1B-BMODE0)") (class "Default")
      (node (ref "R210") (pin "2") (pinfunction "2_2") (pintype "passive"))
      (node (ref "S200") (pin "1") (pinfunction "1_1") (pintype "passive"))
      (node (ref "U1") (pin "42") (pinfunction "BMODE0_42") (pintype "passive"))
    )
    (net (code "45") (name "Net-(U1B-BMODE1)") (class "Default")
      (node (ref "R209") (pin "2") (pinfunction "2_2") (pintype "passive"))
      (node (ref "S200") (pin "2") (pinfunction "2_2") (pintype "passive"))
      (node (ref "U1") (pin "41") (pinfunction "BMODE1_41") (pintype "passive"))
    )
    (net (code "46") (name "Net-(U1B-BMODE2)") (class "Default")
      (node (ref "R208") (pin "2") (pinfunction "2_2") (pintype "passive"))
      (node (ref "S200") (pin "3") (pinfunction "3_3") (pintype "passive"))
      (node (ref "U1") (pin "40") (pinfunction "BMODE2_40") (pintype "passive"))
    )
    (net (code "47") (name "Net-(U1B-PH7{slash}DR1SEC{slash}UART1_RX{slash}TMR7{slash}TACI2)") (class "Default")
      (node (ref "R206") (pin "2") (pinfunction "2_2") (pintype "passive"))
      (node (ref "U1") (pin "153") (pinfunction "PH7/DR1SEC/UART1_RX/TMR7/TACI2_153") (pintype "passive"))
    )
    (net (code "48") (name "Net-(U1B-PJ0{slash}SCL)") (class "Default")
      (node (ref "R202") (pin "2") (pinfunction "2_2") (pintype "passive"))
      (node (ref "U1") (pin "173") (pinfunction "PJ0/SCL_173") (pintype "passive"))
    )
    (net (code "49") (name "Net-(U1B-PJ1{slash}SDA)") (class "Default")
      (node (ref "R203") (pin "2") (pinfunction "2_2") (pintype "passive"))
      (node (ref "U1") (pin "172") (pinfunction "PJ1/SDA_172") (pintype "passive"))
    )
    (net (code "50") (name "Net-(U203-3V3OUT)") (class "Default")
      (node (ref "C209") (pin "1") (pinfunction "1_1") (pintype "passive"))
      (node (ref "U203") (pin "6") (pinfunction "3V3OUT_6") (pintype "output"))
    )
    (net (code "51") (name "Net-(U203-ADBUS0)") (class "Default")
      (node (ref "R220") (pin "1") (pinfunction "1_1") (pintype "passive"))
      (node (ref "U203") (pin "24") (pinfunction "ADBUS0_24") (pintype "bidirectional"))
    )
    (net (code "52") (name "Net-(U203-ADBUS1)") (class "Default")
      (node (ref "R221") (pin "1") (pinfunction "1_1") (pintype "passive"))
      (node (ref "U203") (pin "23") (pinfunction "ADBUS1_23") (pintype "bidirectional"))
    )
    (net (code "53") (name "Net-(U203-ADBUS2)") (class "Default")
      (node (ref "R222") (pin "1") (pinfunction "1_1") (pintype "passive"))
      (node (ref "U203") (pin "22") (pinfunction "ADBUS2_22") (pintype "bidirectional"))
    )
    (net (code "54") (name "Net-(U203-ADBUS3)") (class "Default")
      (node (ref "R223") (pin "1") (pinfunction "1_1") (pintype "passive"))
      (node (ref "U203") (pin "21") (pinfunction "ADBUS3_21") (pintype "bidirectional"))
    )
    (net (code "55") (name "Net-(U203-ADBUS4)") (class "Default")
      (node (ref "R225") (pin "1") (pinfunction "1_1") (pintype "passive"))
      (node (ref "U203") (pin "20") (pinfunction "ADBUS4_20") (pintype "bidirectional"))
    )
    (net (code "56") (name "Net-(U203-ADBUS5)") (class "Default")
      (node (ref "R227") (pin "1") (pinfunction "1_1") (pintype "passive"))
      (node (ref "U203") (pin "19") (pinfunction "ADBUS5_19") (pintype "bidirectional"))
    )
    (net (code "57") (name "Net-(U203-BDBUS0)") (class "Default")
      (node (ref "R232") (pin "1") (pinfunction "1_1") (pintype "passive"))
      (node (ref "U203") (pin "40") (pinfunction "BDBUS0_40") (pintype "bidirectional"))
    )
    (net (code "58") (name "Net-(U203-BDBUS1)") (class "Default")
      (node (ref "R233") (pin "1") (pinfunction "1_1") (pintype "passive"))
      (node (ref "U203") (pin "39") (pinfunction "BDBUS1_39") (pintype "bidirectional"))
    )
    (net (code "59") (name "Net-(U203-EECS)") (class "Default")
      (node (ref "U203") (pin "48") (pinfunction "EECS_48") (pintype "output"))
      (node (ref "U205") (pin "1") (pinfunction "CS_1") (pintype "input"))
    )
    (net (code "60") (name "Net-(U203-EEDATA)") (class "Default")
      (node (ref "R237") (pin "1") (pinfunction "1_1") (pintype "passive"))
      (node (ref "U203") (pin "2") (pinfunction "EEDATA_2") (pintype "bidirectional"))
      (node (ref "U205") (pin "3") (pinfunction "SDI_3") (pintype "input"))
    )
    (net (code "61") (name "Net-(U203-EESK)") (class "Default")
      (node (ref "U203") (pin "1") (pinfunction "EESK_1") (pintype "output"))
      (node (ref "U205") (pin "2") (pinfunction "SCLK_2") (pintype "input"))
    )
    (net (code "62") (name "Net-(U203-SI{slash}WUA)") (class "Default")
      (node (ref "R230") (pin "2") (pinfunction "2_2") (pintype "passive"))
      (node (ref "U203") (pin "10") (pinfunction "SI/WUA_10") (pintype "input"))
    )
    (net (code "63") (name "Net-(U203-SI{slash}WUB)") (class "Default")
      (node (ref "R236") (pin "2") (pinfunction "2_2") (pintype "passive"))
      (node (ref "U203") (pin "26") (pinfunction "SI/WUB_26") (pintype "input"))
    )
    (net (code "64") (name "Net-(U203-XTIN)") (class "Default")
      (node (ref "C211") (pin "1") (pinfunction "1_1") (pintype "passive"))
      (node (ref "U203") (pin "43") (pinfunction "XTIN_43") (pintype "passive"))
      (node (ref "X200") (pin "2") (pinfunction "OSC2_2") (pintype "passive"))
    )
    (net (code "65") (name "Net-(U203-XTOUT)") (class "Default")
      (node (ref "C212") (pin "1") (pinfunction "1_1") (pintype "passive"))
      (node (ref "U203") (pin "44") (pinfunction "XTOUT_44") (pintype "passive"))
      (node (ref "X200") (pin "1") (pinfunction "OSC1_1") (pintype "passive"))
    )
    (net (code "66") (name "Net-(U203-~{RESET})") (class "Default")
      (node (ref "R234") (pin "2") (pinfunction "2_2") (pintype "passive"))
      (node (ref "U203") (pin "4") (pinfunction "~{RESET}_4") (pintype "input"))
    )
    (net (code "67") (name "Net-(U203-~{RSTOUT})") (class "Default")
      (node (ref "R228") (pin "2") (pinfunction "2_2") (pintype "passive"))
      (node (ref "U203") (pin "5") (pinfunction "~{RSTOUT}_5") (pintype "output"))
    )
    (net (code "68") (name "Net-(U204-C1+)") (class "Default")
      (node (ref "C213") (pin "2") (pinfunction "2_2") (pintype "passive"))
      (node (ref "U204") (pin "1") (pinfunction "C1+_1") (pintype "power_in"))
    )
    (net (code "69") (name "Net-(U204-C1-)") (class "Default")
      (node (ref "C213") (pin "1") (pinfunction "1_1") (pintype "passive"))
      (node (ref "U204") (pin "3") (pinfunction "C1-_3") (pintype "power_in"))
    )
    (net (code "70") (name "Net-(U204-C2+)") (class "Default")
      (node (ref "C214") (pin "2") (pinfunction "2_2") (pintype "passive"))
      (node (ref "U204") (pin "4") (pinfunction "C2+_4") (pintype "power_in"))
    )
    (net (code "71") (name "Net-(U204-C2-)") (class "Default")
      (node (ref "C214") (pin "1") (pinfunction "1_1") (pintype "passive"))
      (node (ref "U204") (pin "5") (pinfunction "C2-_5") (pintype "power_in"))
    )
    (net (code "72") (name "Net-(U204-DIN1)") (class "Default")
      (node (ref "R229") (pin "2") (pinfunction "2_2") (pintype "passive"))
      (node (ref "U204") (pin "11") (pinfunction "DIN1_11") (pintype "input"))
    )
    (net (code "73") (name "Net-(U204-ROUT1)") (class "Default")
      (node (ref "R231") (pin "2") (pinfunction "2_2") (pintype "passive"))
      (node (ref "U204") (pin "12") (pinfunction "ROUT1_12") (pintype "output"))
    )
    (net (code "74") (name "Net-(U204-V+)") (class "Default")
      (node (ref "C215") (pin "2") (pinfunction "2_2") (pintype "passive"))
      (node (ref "U204") (pin "2") (pinfunction "V+_2") (pintype "power_in"))
    )
    (net (code "75") (name "Net-(U204-V-)") (class "Default")
      (node (ref "C216") (pin "2") (pinfunction "2_2") (pintype "passive"))
      (node (ref "U204") (pin "6") (pinfunction "V-_6") (pintype "power_in"))
    )
    (net (code "76") (name "Net-(U205-SDO)") (class "Default")
      (node (ref "R235") (pin "1") (pinfunction "1_1") (pintype "passive"))
      (node (ref "R237") (pin "2") (pinfunction "2_2") (pintype "passive"))
      (node (ref "U205") (pin "4") (pinfunction "SDO_4") (pintype "output"))
    )
    (net (code "77") (name "VCC3V3") (class "Default")
      (node (ref "C200") (pin "2") (pinfunction "2_2") (pintype "passive"))
      (node (ref "C210") (pin "2") (pinfunction "2_2") (pintype "passive"))
      (node (ref "C218") (pin "2") (pinfunction "2_2") (pintype "passive"))
      (node (ref "CON200") (pin "4") (pinfunction "VDD_4") (pintype "passive"))
      (node (ref "R200") (pin "2") (pinfunction "2_2") (pintype "passive"))
      (node (ref "R201") (pin "2") (pinfunction "2_2") (pintype "passive"))
      (node (ref "R207") (pin "1") (pinfunction "1_1") (pintype "passive"))
      (node (ref "R211") (pin "2") (pinfunction "2_2") (pintype "passive"))
      (node (ref "R212") (pin "2") (pinfunction "2_2") (pintype "passive"))
      (node (ref "R213") (pin "2") (pinfunction "2_2") (pintype "passive"))
      (node (ref "R214") (pin "2") (pinfunction "2_2") (pintype "passive"))
      (node (ref "R215") (pin "2") (pinfunction "2_2") (pintype "passive"))
      (node (ref "R238") (pin "2") (pinfunction "2_2") (pintype "passive"))
      (node (ref "R239") (pin "1") (pinfunction "1_1") (pintype "passive"))
      (node (ref "R247") (pin "2") (pinfunction "2_2") (pintype "passive"))
      (node (ref "S200") (pin "4") (pinfunction "4_4") (pintype "passive"))
      (node (ref "S200") (pin "5") (pinfunction "5_5") (pintype "passive"))
      (node (ref "S200") (pin "6") (pinfunction "6_6") (pintype "passive"))
      (node (ref "U201") (pin "8") (pinfunction "VCC_8") (pintype "power_in"))
      (node (ref "U204") (pin "16") (pinfunction "VCC_16") (pintype "power_in"))
    )
    (net (code "78") (name "VCC3V3_USB") (class "Default")
      (node (ref "C203") (pin "2") (pinfunction "2_2") (pintype "passive"))
      (node (ref "R230") (pin "1") (pinfunction "1_1") (pintype "passive"))
      (node (ref "R236") (pin "1") (pinfunction "1_1") (pintype "passive"))
      (node (ref "U202") (pin "2") (pinfunction "OUT_2") (pintype "passive"))
      (node (ref "U203") (pin "14") (pinfunction "VCCIOA_14") (pintype "power_in"))
      (node (ref "U203") (pin "31") (pinfunction "VCCIOB_31") (pintype "power_in"))
    )
    (net (code "79") (name "VCC5V_USB") (class "Default")
      (node (ref "C201") (pin "2") (pinfunction "2_2") (pintype "passive"))
      (node (ref "C202") (pin "2") (pinfunction "2_2") (pintype "passive"))
      (node (ref "C204") (pin "2") (pinfunction "2_2") (pintype "passive"))
      (node (ref "C205") (pin "2") (pinfunction "2_2") (pintype "passive"))
      (node (ref "C206") (pin "2") (pinfunction "2_2") (pintype "passive"))
      (node (ref "C207") (pin "2") (pinfunction "2_2") (pintype "passive"))
      (node (ref "C217") (pin "2") (pinfunction "2_2") (pintype "passive"))
      (node (ref "L200") (pin "2") (pinfunction "2_2") (pintype "passive"))
      (node (ref "R216") (pin "1") (pinfunction "1_1") (pintype "passive"))
      (node (ref "R217") (pin "2") (pinfunction "2_2") (pintype "passive"))
      (node (ref "R235") (pin "2") (pinfunction "2_2") (pintype "passive"))
      (node (ref "U202") (pin "3") (pinfunction "IN_3") (pintype "passive"))
      (node (ref "U203") (pin "3") (pinfunction "VCC_3") (pintype "power_in"))
      (node (ref "U203") (pin "42") (pinfunction "VCC_42") (pintype "power_in"))
      (node (ref "U205") (pin "6") (pinfunction "ORG_6") (pintype "passive"))
      (node (ref "U205") (pin "8") (pinfunction "VCC_8") (pintype "power_in"))
    )
    (net (code "80") (name "unconnected-(CON200-DAT1-Pad8)") (class "Default")
      (node (ref "CON200") (pin "8") (pinfunction "DAT1_8") (pintype "passive+no_connect"))
    )
    (net (code "81") (name "unconnected-(CON200-DAT2-Pad1)") (class "Default")
      (node (ref "CON200") (pin "1") (pinfunction "DAT2_1") (pintype "passive+no_connect"))
    )
    (net (code "82") (name "unconnected-(CON202-NC-Pad3)") (class "Default")
      (node (ref "CON202") (pin "3") (pinfunction "NC_3") (pintype "passive+no_connect"))
    )
    (net (code "83") (name "unconnected-(CON202-NC-Pad4)") (class "Default")
      (node (ref "CON202") (pin "4") (pinfunction "NC_4") (pintype "passive+no_connect"))
    )
    (net (code "84") (name "unconnected-(U203-ACBUS0-Pad15)") (class "Default")
      (node (ref "U203") (pin "15") (pinfunction "ACBUS0_15") (pintype "bidirectional+no_connect"))
    )
    (net (code "85") (name "unconnected-(U203-ACBUS1-Pad13)") (class "Default")
      (node (ref "U203") (pin "13") (pinfunction "ACBUS1_13") (pintype "bidirectional+no_connect"))
    )
    (net (code "86") (name "unconnected-(U203-ACBUS2-Pad12)") (class "Default")
      (node (ref "U203") (pin "12") (pinfunction "ACBUS2_12") (pintype "bidirectional+no_connect"))
    )
    (net (code "87") (name "unconnected-(U203-ACBUS3-Pad11)") (class "Default")
      (node (ref "U203") (pin "11") (pinfunction "ACBUS3_11") (pintype "bidirectional+no_connect"))
    )
    (net (code "88") (name "unconnected-(U203-ADBUS6-Pad17)") (class "Default")
      (node (ref "U203") (pin "17") (pinfunction "ADBUS6_17") (pintype "bidirectional+no_connect"))
    )
    (net (code "89") (name "unconnected-(U203-ADBUS7-Pad16)") (class "Default")
      (node (ref "U203") (pin "16") (pinfunction "ADBUS7_16") (pintype "bidirectional+no_connect"))
    )
    (net (code "90") (name "unconnected-(U203-BCBUS0-Pad30)") (class "Default")
      (node (ref "U203") (pin "30") (pinfunction "BCBUS0_30") (pintype "bidirectional+no_connect"))
    )
    (net (code "91") (name "unconnected-(U203-BCBUS1-Pad29)") (class "Default")
      (node (ref "U203") (pin "29") (pinfunction "BCBUS1_29") (pintype "bidirectional+no_connect"))
    )
    (net (code "92") (name "unconnected-(U203-BCBUS2-Pad28)") (class "Default")
      (node (ref "U203") (pin "28") (pinfunction "BCBUS2_28") (pintype "bidirectional+no_connect"))
    )
    (net (code "93") (name "unconnected-(U203-BCBUS3-Pad27)") (class "Default")
      (node (ref "U203") (pin "27") (pinfunction "BCBUS3_27") (pintype "bidirectional+no_connect"))
    )
    (net (code "94") (name "unconnected-(U203-BDBUS2-Pad38)") (class "Default")
      (node (ref "U203") (pin "38") (pinfunction "BDBUS2_38") (pintype "bidirectional+no_connect"))
    )
    (net (code "95") (name "unconnected-(U203-BDBUS3-Pad37)") (class "Default")
      (node (ref "U203") (pin "37") (pinfunction "BDBUS3_37") (pintype "bidirectional+no_connect"))
    )
    (net (code "96") (name "unconnected-(U203-BDBUS4-Pad36)") (class "Default")
      (node (ref "U203") (pin "36") (pinfunction "BDBUS4_36") (pintype "bidirectional+no_connect"))
    )
    (net (code "97") (name "unconnected-(U203-BDBUS5-Pad35)") (class "Default")
      (node (ref "U203") (pin "35") (pinfunction "BDBUS5_35") (pintype "bidirectional+no_connect"))
    )
    (net (code "98") (name "unconnected-(U203-BDBUS6-Pad33)") (class "Default")
      (node (ref "U203") (pin "33") (pinfunction "BDBUS6_33") (pintype "bidirectional+no_connect"))
    )
    (net (code "99") (name "unconnected-(U203-BDBUS7-Pad32)") (class "Default")
      (node (ref "U203") (pin "32") (pinfunction "BDBUS7_32") (pintype "bidirectional+no_connect"))
    )
    (net (code "100") (name "unconnected-(U203-~{PWREN}-Pad41)") (class "Default")
      (node (ref "U203") (pin "41") (pinfunction "~{PWREN}_41") (pintype "output+no_connect"))
    )
    (net (code "101") (name "unconnected-(U204-DIN2-Pad10)") (class "Default")
      (node (ref "U204") (pin "10") (pinfunction "DIN2_10") (pintype "input+no_connect"))
    )
    (net (code "102") (name "unconnected-(U204-DOUT2-Pad7)") (class "Default")
      (node (ref "U204") (pin "7") (pinfunction "DOUT2_7") (pintype "output+no_connect"))
    )
    (net (code "103") (name "unconnected-(U204-RIN2-Pad8)") (class "Default")
      (node (ref "U204") (pin "8") (pinfunction "RIN2_8") (pintype "input+no_connect"))
    )
    (net (code "104") (name "unconnected-(U204-ROUT2-Pad9)") (class "Default")
      (node (ref "U204") (pin "9") (pinfunction "ROUT2_9") (pintype "output+no_connect"))
    )
    (net (code "105") (name "unconnected-(U205-NC-Pad7)") (class "Default")
      (node (ref "U205") (pin "7") (pinfunction "NC_7") (pintype "passive+no_connect"))
    )
  )
)
